# 04_-_DRIVERS.net
KiCad netlist of a schematic drawn in Altium Designer
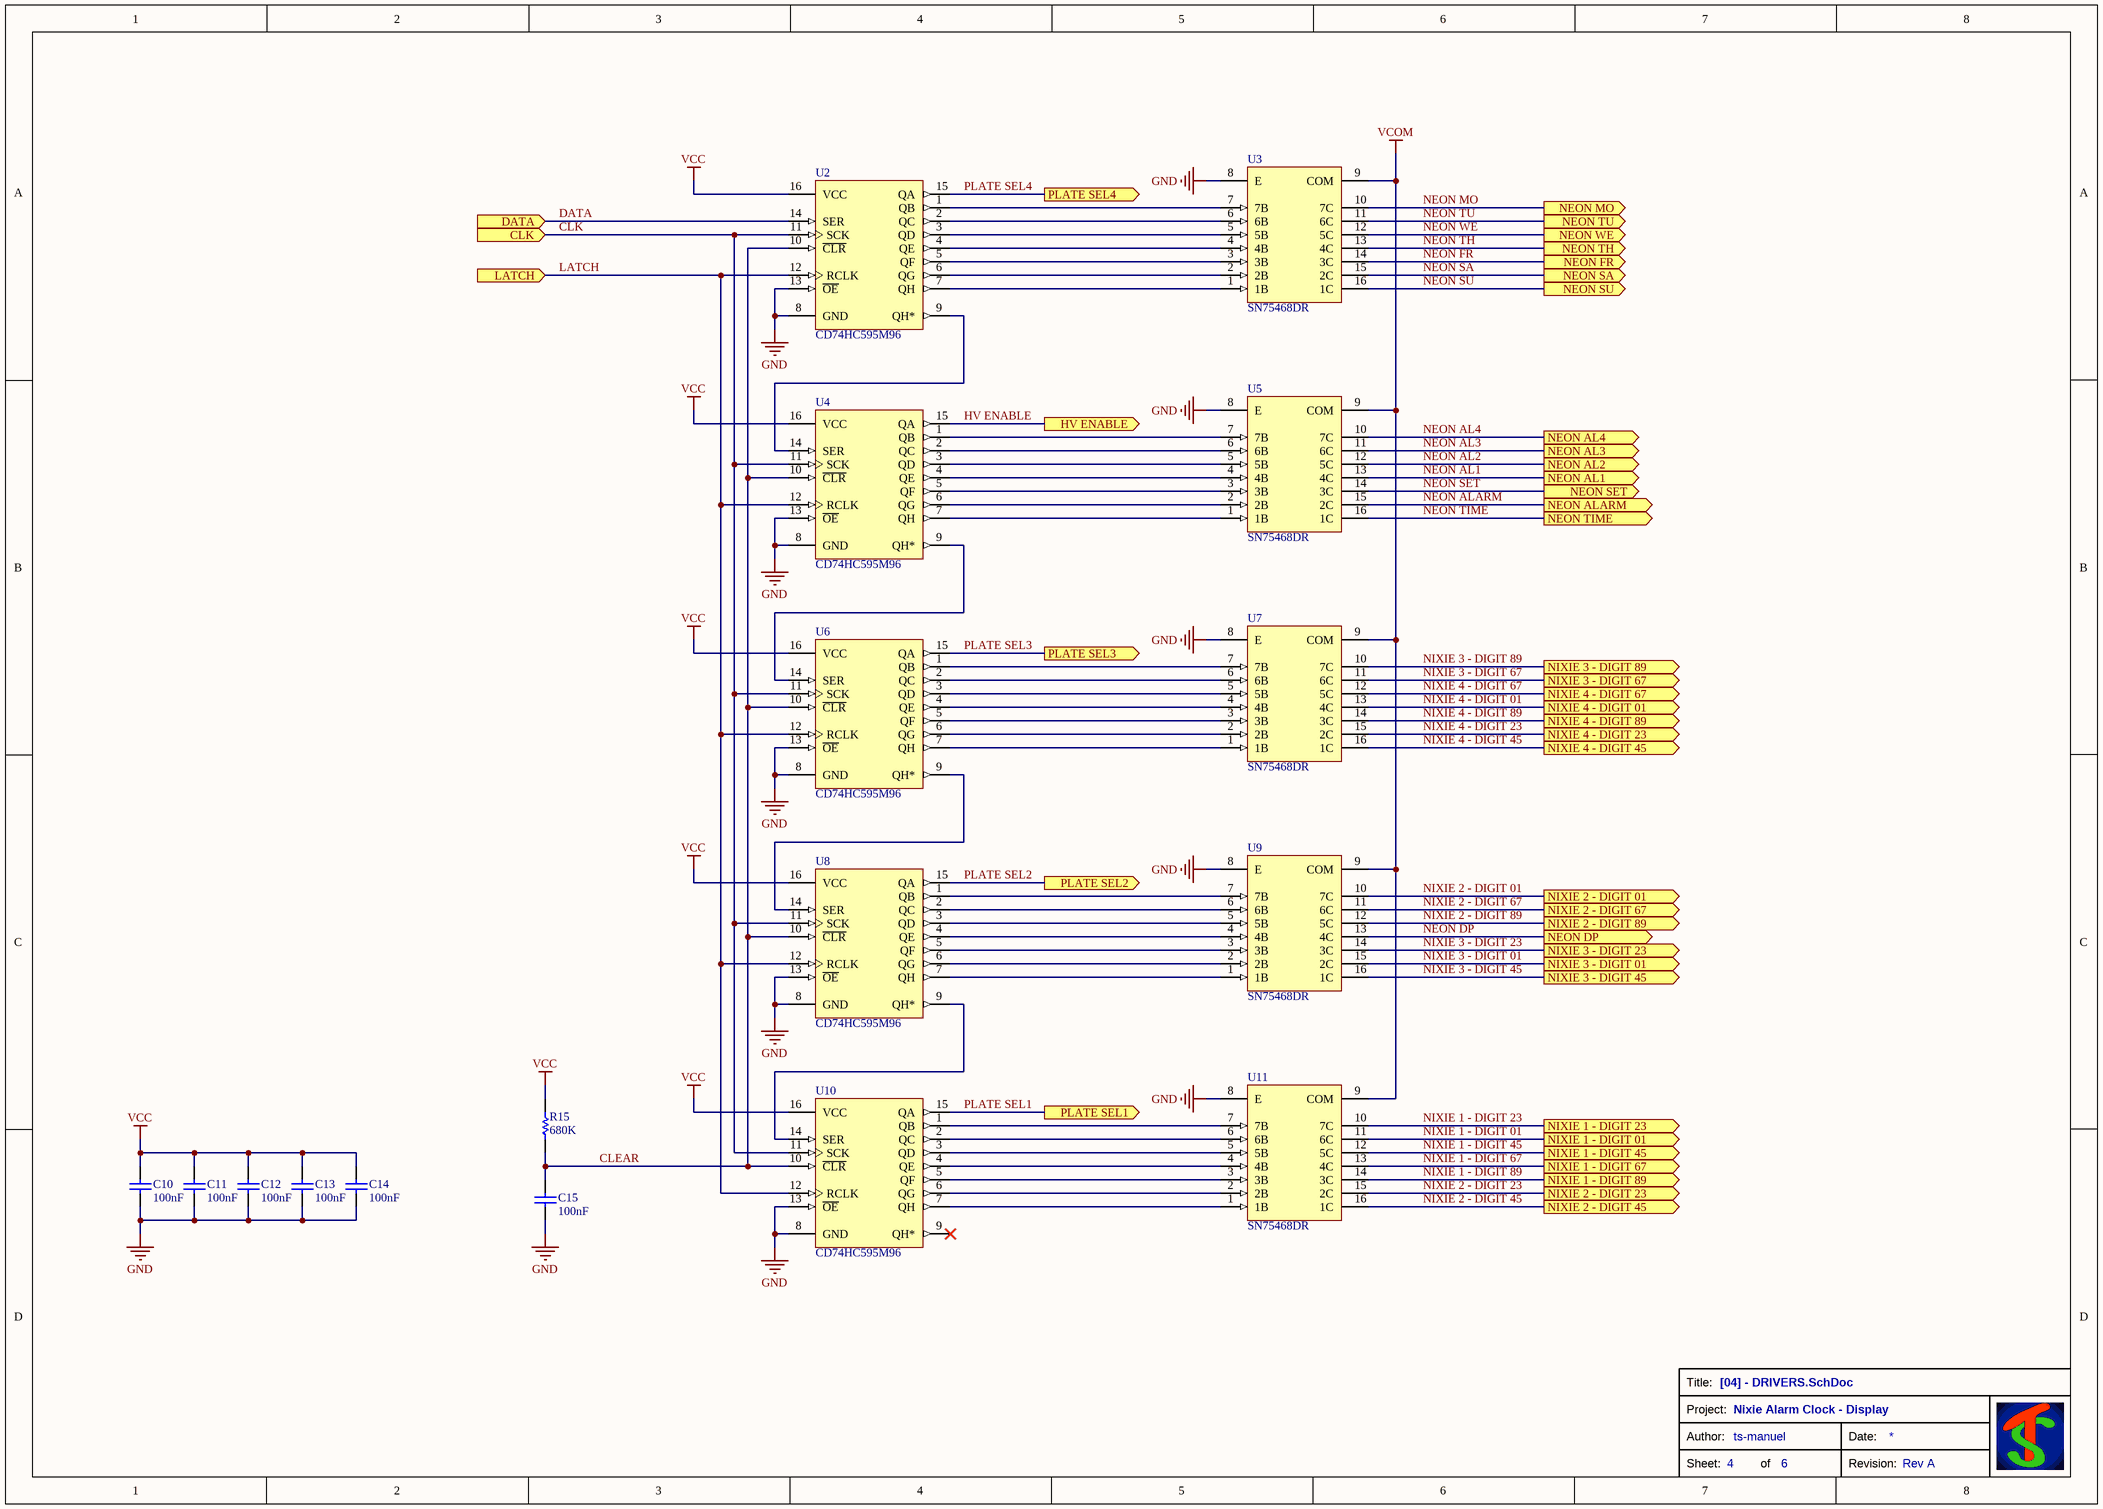
[diagram p0: [04] - DRIVERS.SchDoc]

(export (version "E")
  (design (tool "Eeschema 10.0.6"))
  (components
    (comp (ref "C10")
      (value "100nF")
      (footprint "CAP-1206")
      (description "Condensatori in ceramica multistrato MLCC - SMD/SMT WCAP-CSMH 200V 0.1uF 1206 10%")
      (fields (field (name "MANUFACTURER") "KEMET") (field (name "TOLERANCE") "20%"))
      (libsource (lib "mt_local_library") (part "CAP-1206-100n-885342208002"))
    )
    (comp (ref "C11")
      (value "100nF")
      (footprint "CAP-1206")
      (description "Condensatori in ceramica multistrato MLCC - SMD/SMT WCAP-CSMH 200V 0.1uF 1206 10%")
      (fields (field (name "MANUFACTURER") "KEMET") (field (name "TOLERANCE") "20%"))
      (libsource (lib "mt_local_library") (part "CAP-1206-100n-885342208002"))
    )
    (comp (ref "C12")
      (value "100nF")
      (footprint "CAP-1206")
      (description "Condensatori in ceramica multistrato MLCC - SMD/SMT WCAP-CSMH 200V 0.1uF 1206 10%")
      (fields (field (name "MANUFACTURER") "KEMET") (field (name "TOLERANCE") "20%"))
      (libsource (lib "mt_local_library") (part "CAP-1206-100n-885342208002"))
    )
    (comp (ref "C13")
      (value "100nF")
      (footprint "CAP-1206")
      (description "Condensatori in ceramica multistrato MLCC - SMD/SMT WCAP-CSMH 200V 0.1uF 1206 10%")
      (fields (field (name "MANUFACTURER") "KEMET") (field (name "TOLERANCE") "20%"))
      (libsource (lib "mt_local_library") (part "CAP-1206-100n-885342208002"))
    )
    (comp (ref "C14")
      (value "100nF")
      (footprint "CAP-1206")
      (description "Condensatori in ceramica multistrato MLCC - SMD/SMT WCAP-CSMH 200V 0.1uF 1206 10%")
      (fields (field (name "MANUFACTURER") "KEMET") (field (name "TOLERANCE") "20%"))
      (libsource (lib "mt_local_library") (part "CAP-1206-100n-885342208002"))
    )
    (comp (ref "C15")
      (value "100nF")
      (footprint "CAP-1206")
      (description "Condensatori in ceramica multistrato MLCC - SMD/SMT WCAP-CSMH 200V 0.1uF 1206 10%")
      (fields (field (name "MANUFACTURER") "KEMET") (field (name "TOLERANCE") "20%"))
      (libsource (lib "mt_local_library") (part "CAP-1206-100n-885342208002"))
    )
    (comp (ref "R15")
      (value "680K")
      (footprint "RES-1206")
      (description "Thin Film Resistors 680K OHM 1% 50PPM 1/4W")
      (fields (field (name "MANUFACTURER") "Yageo") (field (name "TOLERANCE") "1%"))
      (libsource (lib "mt_local_library") (part "RES-1206-680K-RT1206FRE07680KL"))
    )
    (comp (ref "U2")
      (value "CD74HC595M96")
      (footprint "SOIC127P600X175-16N")
      (description "8-Bit Shift Register")
      (libsource (lib "mt_local_library") (part "CD74HC595"))
    )
    (comp (ref "U3")
      (value "SN75468DR")
      (footprint "SOIC127P600X175-16N")
      (description "High Voltage Darlington Transistor Arrays")
      (libsource (lib "mt_local_library") (part "SN75468"))
    )
    (comp (ref "U4")
      (value "CD74HC595M96")
      (footprint "SOIC127P600X175-16N")
      (description "8-Bit Shift Register")
      (libsource (lib "mt_local_library") (part "CD74HC595"))
    )
    (comp (ref "U5")
      (value "SN75468DR")
      (footprint "SOIC127P600X175-16N")
      (description "High Voltage Darlington Transistor Arrays")
      (libsource (lib "mt_local_library") (part "SN75468"))
    )
    (comp (ref "U6")
      (value "CD74HC595M96")
      (footprint "SOIC127P600X175-16N")
      (description "8-Bit Shift Register")
      (libsource (lib "mt_local_library") (part "CD74HC595"))
    )
    (comp (ref "U7")
      (value "SN75468DR")
      (footprint "SOIC127P600X175-16N")
      (description "High Voltage Darlington Transistor Arrays")
      (libsource (lib "mt_local_library") (part "SN75468"))
    )
    (comp (ref "U8")
      (value "CD74HC595M96")
      (footprint "SOIC127P600X175-16N")
      (description "8-Bit Shift Register")
      (libsource (lib "mt_local_library") (part "CD74HC595"))
    )
    (comp (ref "U9")
      (value "SN75468DR")
      (footprint "SOIC127P600X175-16N")
      (description "High Voltage Darlington Transistor Arrays")
      (libsource (lib "mt_local_library") (part "SN75468"))
    )
    (comp (ref "U10")
      (value "CD74HC595M96")
      (footprint "SOIC127P600X175-16N")
      (description "8-Bit Shift Register")
      (libsource (lib "mt_local_library") (part "CD74HC595"))
    )
    (comp (ref "U11")
      (value "SN75468DR")
      (footprint "SOIC127P600X175-16N")
      (description "High Voltage Darlington Transistor Arrays")
      (libsource (lib "mt_local_library") (part "SN75468"))
    )
  )
  (nets
    (net (code "1") (name "/CLEAR") (class "Default")
      (node (ref "C15") (pin "2") (pinfunction "2_2") (pintype "passive"))
      (node (ref "R15") (pin "1") (pinfunction "1_1") (pintype "passive"))
      (node (ref "U10") (pin "10") (pinfunction "~{CLR}_10") (pintype "input"))
      (node (ref "U2") (pin "10") (pinfunction "~{CLR}_10") (pintype "input"))
      (node (ref "U4") (pin "10") (pinfunction "~{CLR}_10") (pintype "input"))
      (node (ref "U6") (pin "10") (pinfunction "~{CLR}_10") (pintype "input"))
      (node (ref "U8") (pin "10") (pinfunction "~{CLR}_10") (pintype "input"))
    )
    (net (code "2") (name "/CLK") (class "Default")
      (node (ref "U10") (pin "11") (pinfunction "SCK_11") (pintype "input"))
      (node (ref "U2") (pin "11") (pinfunction "SCK_11") (pintype "input"))
      (node (ref "U4") (pin "11") (pinfunction "SCK_11") (pintype "input"))
      (node (ref "U6") (pin "11") (pinfunction "SCK_11") (pintype "input"))
      (node (ref "U8") (pin "11") (pinfunction "SCK_11") (pintype "input"))
    )
    (net (code "3") (name "/DATA") (class "Default")
      (node (ref "U2") (pin "14") (pinfunction "SER_14") (pintype "input"))
    )
    (net (code "4") (name "/HV ENABLE") (class "Default")
      (node (ref "U4") (pin "15") (pinfunction "QA_15") (pintype "output"))
    )
    (net (code "5") (name "/LATCH") (class "Default")
      (node (ref "U10") (pin "12") (pinfunction "RCLK_12") (pintype "input"))
      (node (ref "U2") (pin "12") (pinfunction "RCLK_12") (pintype "input"))
      (node (ref "U4") (pin "12") (pinfunction "RCLK_12") (pintype "input"))
      (node (ref "U6") (pin "12") (pinfunction "RCLK_12") (pintype "input"))
      (node (ref "U8") (pin "12") (pinfunction "RCLK_12") (pintype "input"))
    )
    (net (code "6") (name "/NEON AL1") (class "Default")
      (node (ref "U5") (pin "13") (pinfunction "4C_13") (pintype "open_collector"))
    )
    (net (code "7") (name "/NEON AL2") (class "Default")
      (node (ref "U5") (pin "12") (pinfunction "5C_12") (pintype "open_collector"))
    )
    (net (code "8") (name "/NEON AL3") (class "Default")
      (node (ref "U5") (pin "11") (pinfunction "6C_11") (pintype "open_collector"))
    )
    (net (code "9") (name "/NEON AL4") (class "Default")
      (node (ref "U5") (pin "10") (pinfunction "7C_10") (pintype "open_collector"))
    )
    (net (code "10") (name "/NEON ALARM") (class "Default")
      (node (ref "U5") (pin "15") (pinfunction "2C_15") (pintype "open_collector"))
    )
    (net (code "11") (name "/NEON DP") (class "Default")
      (node (ref "U9") (pin "13") (pinfunction "4C_13") (pintype "open_collector"))
    )
    (net (code "12") (name "/NEON FR") (class "Default")
      (node (ref "U3") (pin "14") (pinfunction "3C_14") (pintype "open_collector"))
    )
    (net (code "13") (name "/NEON MO") (class "Default")
      (node (ref "U3") (pin "10") (pinfunction "7C_10") (pintype "open_collector"))
    )
    (net (code "14") (name "/NEON SA") (class "Default")
      (node (ref "U3") (pin "15") (pinfunction "2C_15") (pintype "open_collector"))
    )
    (net (code "15") (name "/NEON SET") (class "Default")
      (node (ref "U5") (pin "14") (pinfunction "3C_14") (pintype "open_collector"))
    )
    (net (code "16") (name "/NEON SU") (class "Default")
      (node (ref "U3") (pin "16") (pinfunction "1C_16") (pintype "open_collector"))
    )
    (net (code "17") (name "/NEON TH") (class "Default")
      (node (ref "U3") (pin "13") (pinfunction "4C_13") (pintype "open_collector"))
    )
    (net (code "18") (name "/NEON TIME") (class "Default")
      (node (ref "U5") (pin "16") (pinfunction "1C_16") (pintype "open_collector"))
    )
    (net (code "19") (name "/NEON TU") (class "Default")
      (node (ref "U3") (pin "11") (pinfunction "6C_11") (pintype "open_collector"))
    )
    (net (code "20") (name "/NEON WE") (class "Default")
      (node (ref "U3") (pin "12") (pinfunction "5C_12") (pintype "open_collector"))
    )
    (net (code "21") (name "/NIXIE 1 - DIGIT 01") (class "Default")
      (node (ref "U11") (pin "11") (pinfunction "6C_11") (pintype "open_collector"))
    )
    (net (code "22") (name "/NIXIE 1 - DIGIT 23") (class "Default")
      (node (ref "U11") (pin "10") (pinfunction "7C_10") (pintype "open_collector"))
    )
    (net (code "23") (name "/NIXIE 1 - DIGIT 45") (class "Default")
      (node (ref "U11") (pin "12") (pinfunction "5C_12") (pintype "open_collector"))
    )
    (net (code "24") (name "/NIXIE 1 - DIGIT 67") (class "Default")
      (node (ref "U11") (pin "13") (pinfunction "4C_13") (pintype "open_collector"))
    )
    (net (code "25") (name "/NIXIE 1 - DIGIT 89") (class "Default")
      (node (ref "U11") (pin "14") (pinfunction "3C_14") (pintype "open_collector"))
    )
    (net (code "26") (name "/NIXIE 2 - DIGIT 01") (class "Default")
      (node (ref "U9") (pin "10") (pinfunction "7C_10") (pintype "open_collector"))
    )
    (net (code "27") (name "/NIXIE 2 - DIGIT 23") (class "Default")
      (node (ref "U11") (pin "15") (pinfunction "2C_15") (pintype "open_collector"))
    )
    (net (code "28") (name "/NIXIE 2 - DIGIT 45") (class "Default")
      (node (ref "U11") (pin "16") (pinfunction "1C_16") (pintype "open_collector"))
    )
    (net (code "29") (name "/NIXIE 2 - DIGIT 67") (class "Default")
      (node (ref "U9") (pin "11") (pinfunction "6C_11") (pintype "open_collector"))
    )
    (net (code "30") (name "/NIXIE 2 - DIGIT 89") (class "Default")
      (node (ref "U9") (pin "12") (pinfunction "5C_12") (pintype "open_collector"))
    )
    (net (code "31") (name "/NIXIE 3 - DIGIT 01") (class "Default")
      (node (ref "U9") (pin "15") (pinfunction "2C_15") (pintype "open_collector"))
    )
    (net (code "32") (name "/NIXIE 3 - DIGIT 23") (class "Default")
      (node (ref "U9") (pin "14") (pinfunction "3C_14") (pintype "open_collector"))
    )
    (net (code "33") (name "/NIXIE 3 - DIGIT 45") (class "Default")
      (node (ref "U9") (pin "16") (pinfunction "1C_16") (pintype "open_collector"))
    )
    (net (code "34") (name "/NIXIE 3 - DIGIT 67") (class "Default")
      (node (ref "U7") (pin "11") (pinfunction "6C_11") (pintype "open_collector"))
    )
    (net (code "35") (name "/NIXIE 3 - DIGIT 89") (class "Default")
      (node (ref "U7") (pin "10") (pinfunction "7C_10") (pintype "open_collector"))
    )
    (net (code "36") (name "/NIXIE 4 - DIGIT 01") (class "Default")
      (node (ref "U7") (pin "13") (pinfunction "4C_13") (pintype "open_collector"))
    )
    (net (code "37") (name "/NIXIE 4 - DIGIT 23") (class "Default")
      (node (ref "U7") (pin "15") (pinfunction "2C_15") (pintype "open_collector"))
    )
    (net (code "38") (name "/NIXIE 4 - DIGIT 45") (class "Default")
      (node (ref "U7") (pin "16") (pinfunction "1C_16") (pintype "open_collector"))
    )
    (net (code "39") (name "/NIXIE 4 - DIGIT 67") (class "Default")
      (node (ref "U7") (pin "12") (pinfunction "5C_12") (pintype "open_collector"))
    )
    (net (code "40") (name "/NIXIE 4 - DIGIT 89") (class "Default")
      (node (ref "U7") (pin "14") (pinfunction "3C_14") (pintype "open_collector"))
    )
    (net (code "41") (name "/PLATE SEL1") (class "Default")
      (node (ref "U10") (pin "15") (pinfunction "QA_15") (pintype "output"))
    )
    (net (code "42") (name "/PLATE SEL2") (class "Default")
      (node (ref "U8") (pin "15") (pinfunction "QA_15") (pintype "output"))
    )
    (net (code "43") (name "/PLATE SEL3") (class "Default")
      (node (ref "U6") (pin "15") (pinfunction "QA_15") (pintype "output"))
    )
    (net (code "44") (name "/PLATE SEL4") (class "Default")
      (node (ref "U2") (pin "15") (pinfunction "QA_15") (pintype "output"))
    )
    (net (code "45") (name "GND") (class "Default")
      (node (ref "C10") (pin "1") (pinfunction "1_1") (pintype "passive"))
      (node (ref "C11") (pin "1") (pinfunction "1_1") (pintype "passive"))
      (node (ref "C12") (pin "1") (pinfunction "1_1") (pintype "passive"))
      (node (ref "C13") (pin "1") (pinfunction "1_1") (pintype "passive"))
      (node (ref "C14") (pin "1") (pinfunction "1_1") (pintype "passive"))
      (node (ref "C15") (pin "1") (pinfunction "1_1") (pintype "passive"))
      (node (ref "U10") (pin "13") (pinfunction "~{OE}_13") (pintype "input"))
      (node (ref "U10") (pin "8") (pinfunction "GND_8") (pintype "power_in"))
      (node (ref "U11") (pin "8") (pinfunction "E_8") (pintype "power_in"))
      (node (ref "U2") (pin "13") (pinfunction "~{OE}_13") (pintype "input"))
      (node (ref "U2") (pin "8") (pinfunction "GND_8") (pintype "power_in"))
      (node (ref "U3") (pin "8") (pinfunction "E_8") (pintype "power_in"))
      (node (ref "U4") (pin "13") (pinfunction "~{OE}_13") (pintype "input"))
      (node (ref "U4") (pin "8") (pinfunction "GND_8") (pintype "power_in"))
      (node (ref "U5") (pin "8") (pinfunction "E_8") (pintype "power_in"))
      (node (ref "U6") (pin "13") (pinfunction "~{OE}_13") (pintype "input"))
      (node (ref "U6") (pin "8") (pinfunction "GND_8") (pintype "power_in"))
      (node (ref "U7") (pin "8") (pinfunction "E_8") (pintype "power_in"))
      (node (ref "U8") (pin "13") (pinfunction "~{OE}_13") (pintype "input"))
      (node (ref "U8") (pin "8") (pinfunction "GND_8") (pintype "power_in"))
      (node (ref "U9") (pin "8") (pinfunction "E_8") (pintype "power_in"))
    )
    (net (code "46") (name "Net-(U2-QB)") (class "Default")
      (node (ref "U2") (pin "1") (pinfunction "QB_1") (pintype "output"))
      (node (ref "U3") (pin "7") (pinfunction "7B_7") (pintype "input"))
    )
    (net (code "47") (name "Net-(U2-QC)") (class "Default")
      (node (ref "U2") (pin "2") (pinfunction "QC_2") (pintype "output"))
      (node (ref "U3") (pin "6") (pinfunction "6B_6") (pintype "input"))
    )
    (net (code "48") (name "Net-(U2-QD)") (class "Default")
      (node (ref "U2") (pin "3") (pinfunction "QD_3") (pintype "output"))
      (node (ref "U3") (pin "5") (pinfunction "5B_5") (pintype "input"))
    )
    (net (code "49") (name "Net-(U2-QE)") (class "Default")
      (node (ref "U2") (pin "4") (pinfunction "QE_4") (pintype "output"))
      (node (ref "U3") (pin "4") (pinfunction "4B_4") (pintype "input"))
    )
    (net (code "50") (name "Net-(U2-QF)") (class "Default")
      (node (ref "U2") (pin "5") (pinfunction "QF_5") (pintype "output"))
      (node (ref "U3") (pin "3") (pinfunction "3B_3") (pintype "input"))
    )
    (net (code "51") (name "Net-(U2-QG)") (class "Default")
      (node (ref "U2") (pin "6") (pinfunction "QG_6") (pintype "output"))
      (node (ref "U3") (pin "2") (pinfunction "2B_2") (pintype "input"))
    )
    (net (code "52") (name "Net-(U2-QH)") (class "Default")
      (node (ref "U2") (pin "7") (pinfunction "QH_7") (pintype "output"))
      (node (ref "U3") (pin "1") (pinfunction "1B_1") (pintype "input"))
    )
    (net (code "53") (name "Net-(U2-QH*)") (class "Default")
      (node (ref "U2") (pin "9") (pinfunction "QH*_9") (pintype "output"))
      (node (ref "U4") (pin "14") (pinfunction "SER_14") (pintype "input"))
    )
    (net (code "54") (name "Net-(U4-QB)") (class "Default")
      (node (ref "U4") (pin "1") (pinfunction "QB_1") (pintype "output"))
      (node (ref "U5") (pin "7") (pinfunction "7B_7") (pintype "input"))
    )
    (net (code "55") (name "Net-(U4-QC)") (class "Default")
      (node (ref "U4") (pin "2") (pinfunction "QC_2") (pintype "output"))
      (node (ref "U5") (pin "6") (pinfunction "6B_6") (pintype "input"))
    )
    (net (code "56") (name "Net-(U4-QD)") (class "Default")
      (node (ref "U4") (pin "3") (pinfunction "QD_3") (pintype "output"))
      (node (ref "U5") (pin "5") (pinfunction "5B_5") (pintype "input"))
    )
    (net (code "57") (name "Net-(U4-QE)") (class "Default")
      (node (ref "U4") (pin "4") (pinfunction "QE_4") (pintype "output"))
      (node (ref "U5") (pin "4") (pinfunction "4B_4") (pintype "input"))
    )
    (net (code "58") (name "Net-(U4-QF)") (class "Default")
      (node (ref "U4") (pin "5") (pinfunction "QF_5") (pintype "output"))
      (node (ref "U5") (pin "3") (pinfunction "3B_3") (pintype "input"))
    )
    (net (code "59") (name "Net-(U4-QG)") (class "Default")
      (node (ref "U4") (pin "6") (pinfunction "QG_6") (pintype "output"))
      (node (ref "U5") (pin "2") (pinfunction "2B_2") (pintype "input"))
    )
    (net (code "60") (name "Net-(U4-QH)") (class "Default")
      (node (ref "U4") (pin "7") (pinfunction "QH_7") (pintype "output"))
      (node (ref "U5") (pin "1") (pinfunction "1B_1") (pintype "input"))
    )
    (net (code "61") (name "Net-(U4-QH*)") (class "Default")
      (node (ref "U4") (pin "9") (pinfunction "QH*_9") (pintype "output"))
      (node (ref "U6") (pin "14") (pinfunction "SER_14") (pintype "input"))
    )
    (net (code "62") (name "Net-(U6-QB)") (class "Default")
      (node (ref "U6") (pin "1") (pinfunction "QB_1") (pintype "output"))
      (node (ref "U7") (pin "7") (pinfunction "7B_7") (pintype "input"))
    )
    (net (code "63") (name "Net-(U6-QC)") (class "Default")
      (node (ref "U6") (pin "2") (pinfunction "QC_2") (pintype "output"))
      (node (ref "U7") (pin "6") (pinfunction "6B_6") (pintype "input"))
    )
    (net (code "64") (name "Net-(U6-QD)") (class "Default")
      (node (ref "U6") (pin "3") (pinfunction "QD_3") (pintype "output"))
      (node (ref "U7") (pin "5") (pinfunction "5B_5") (pintype "input"))
    )
    (net (code "65") (name "Net-(U6-QE)") (class "Default")
      (node (ref "U6") (pin "4") (pinfunction "QE_4") (pintype "output"))
      (node (ref "U7") (pin "4") (pinfunction "4B_4") (pintype "input"))
    )
    (net (code "66") (name "Net-(U6-QF)") (class "Default")
      (node (ref "U6") (pin "5") (pinfunction "QF_5") (pintype "output"))
      (node (ref "U7") (pin "3") (pinfunction "3B_3") (pintype "input"))
    )
    (net (code "67") (name "Net-(U6-QG)") (class "Default")
      (node (ref "U6") (pin "6") (pinfunction "QG_6") (pintype "output"))
      (node (ref "U7") (pin "2") (pinfunction "2B_2") (pintype "input"))
    )
    (net (code "68") (name "Net-(U6-QH)") (class "Default")
      (node (ref "U6") (pin "7") (pinfunction "QH_7") (pintype "output"))
      (node (ref "U7") (pin "1") (pinfunction "1B_1") (pintype "input"))
    )
    (net (code "69") (name "Net-(U6-QH*)") (class "Default")
      (node (ref "U6") (pin "9") (pinfunction "QH*_9") (pintype "output"))
      (node (ref "U8") (pin "14") (pinfunction "SER_14") (pintype "input"))
    )
    (net (code "70") (name "Net-(U8-QB)") (class "Default")
      (node (ref "U8") (pin "1") (pinfunction "QB_1") (pintype "output"))
      (node (ref "U9") (pin "7") (pinfunction "7B_7") (pintype "input"))
    )
    (net (code "71") (name "Net-(U8-QC)") (class "Default")
      (node (ref "U8") (pin "2") (pinfunction "QC_2") (pintype "output"))
      (node (ref "U9") (pin "6") (pinfunction "6B_6") (pintype "input"))
    )
    (net (code "72") (name "Net-(U8-QD)") (class "Default")
      (node (ref "U8") (pin "3") (pinfunction "QD_3") (pintype "output"))
      (node (ref "U9") (pin "5") (pinfunction "5B_5") (pintype "input"))
    )
    (net (code "73") (name "Net-(U8-QE)") (class "Default")
      (node (ref "U8") (pin "4") (pinfunction "QE_4") (pintype "output"))
      (node (ref "U9") (pin "4") (pinfunction "4B_4") (pintype "input"))
    )
    (net (code "74") (name "Net-(U8-QF)") (class "Default")
      (node (ref "U8") (pin "5") (pinfunction "QF_5") (pintype "output"))
      (node (ref "U9") (pin "3") (pinfunction "3B_3") (pintype "input"))
    )
    (net (code "75") (name "Net-(U8-QG)") (class "Default")
      (node (ref "U8") (pin "6") (pinfunction "QG_6") (pintype "output"))
      (node (ref "U9") (pin "2") (pinfunction "2B_2") (pintype "input"))
    )
    (net (code "76") (name "Net-(U8-QH)") (class "Default")
      (node (ref "U8") (pin "7") (pinfunction "QH_7") (pintype "output"))
      (node (ref "U9") (pin "1") (pinfunction "1B_1") (pintype "input"))
    )
    (net (code "77") (name "Net-(U10-QB)") (class "Default")
      (node (ref "U10") (pin "1") (pinfunction "QB_1") (pintype "output"))
      (node (ref "U11") (pin "7") (pinfunction "7B_7") (pintype "input"))
    )
    (net (code "78") (name "Net-(U10-QC)") (class "Default")
      (node (ref "U10") (pin "2") (pinfunction "QC_2") (pintype "output"))
      (node (ref "U11") (pin "6") (pinfunction "6B_6") (pintype "input"))
    )
    (net (code "79") (name "Net-(U10-QD)") (class "Default")
      (node (ref "U10") (pin "3") (pinfunction "QD_3") (pintype "output"))
      (node (ref "U11") (pin "5") (pinfunction "5B_5") (pintype "input"))
    )
    (net (code "80") (name "Net-(U10-QE)") (class "Default")
      (node (ref "U10") (pin "4") (pinfunction "QE_4") (pintype "output"))
      (node (ref "U11") (pin "4") (pinfunction "4B_4") (pintype "input"))
    )
    (net (code "81") (name "Net-(U10-QF)") (class "Default")
      (node (ref "U10") (pin "5") (pinfunction "QF_5") (pintype "output"))
      (node (ref "U11") (pin "3") (pinfunction "3B_3") (pintype "input"))
    )
    (net (code "82") (name "Net-(U10-QG)") (class "Default")
      (node (ref "U10") (pin "6") (pinfunction "QG_6") (pintype "output"))
      (node (ref "U11") (pin "2") (pinfunction "2B_2") (pintype "input"))
    )
    (net (code "83") (name "Net-(U10-QH)") (class "Default")
      (node (ref "U10") (pin "7") (pinfunction "QH_7") (pintype "output"))
      (node (ref "U11") (pin "1") (pinfunction "1B_1") (pintype "input"))
    )
    (net (code "84") (name "Net-(U10-SER)") (class "Default")
      (node (ref "U10") (pin "14") (pinfunction "SER_14") (pintype "input"))
      (node (ref "U8") (pin "9") (pinfunction "QH*_9") (pintype "output"))
    )
    (net (code "85") (name "VCC") (class "Default")
      (node (ref "C10") (pin "2") (pinfunction "2_2") (pintype "passive"))
      (node (ref "C11") (pin "2") (pinfunction "2_2") (pintype "passive"))
      (node (ref "C12") (pin "2") (pinfunction "2_2") (pintype "passive"))
      (node (ref "C13") (pin "2") (pinfunction "2_2") (pintype "passive"))
      (node (ref "C14") (pin "2") (pinfunction "2_2") (pintype "passive"))
      (node (ref "R15") (pin "2") (pinfunction "2_2") (pintype "passive"))
      (node (ref "U10") (pin "16") (pinfunction "VCC_16") (pintype "power_in"))
      (node (ref "U2") (pin "16") (pinfunction "VCC_16") (pintype "power_in"))
      (node (ref "U4") (pin "16") (pinfunction "VCC_16") (pintype "power_in"))
      (node (ref "U6") (pin "16") (pinfunction "VCC_16") (pintype "power_in"))
      (node (ref "U8") (pin "16") (pinfunction "VCC_16") (pintype "power_in"))
    )
    (net (code "86") (name "VCOM") (class "Default")
      (node (ref "U11") (pin "9") (pinfunction "COM_9") (pintype "passive"))
      (node (ref "U3") (pin "9") (pinfunction "COM_9") (pintype "passive"))
      (node (ref "U5") (pin "9") (pinfunction "COM_9") (pintype "passive"))
      (node (ref "U7") (pin "9") (pinfunction "COM_9") (pintype "passive"))
      (node (ref "U9") (pin "9") (pinfunction "COM_9") (pintype "passive"))
    )
    (net (code "87") (name "unconnected-(U10-QH*-Pad9)") (class "Default")
      (node (ref "U10") (pin "9") (pinfunction "QH*_9") (pintype "output+no_connect"))
    )
  )
)
